# QuickRotor_V1.net
KiCad netlist of a schematic drawn in Altium Designer
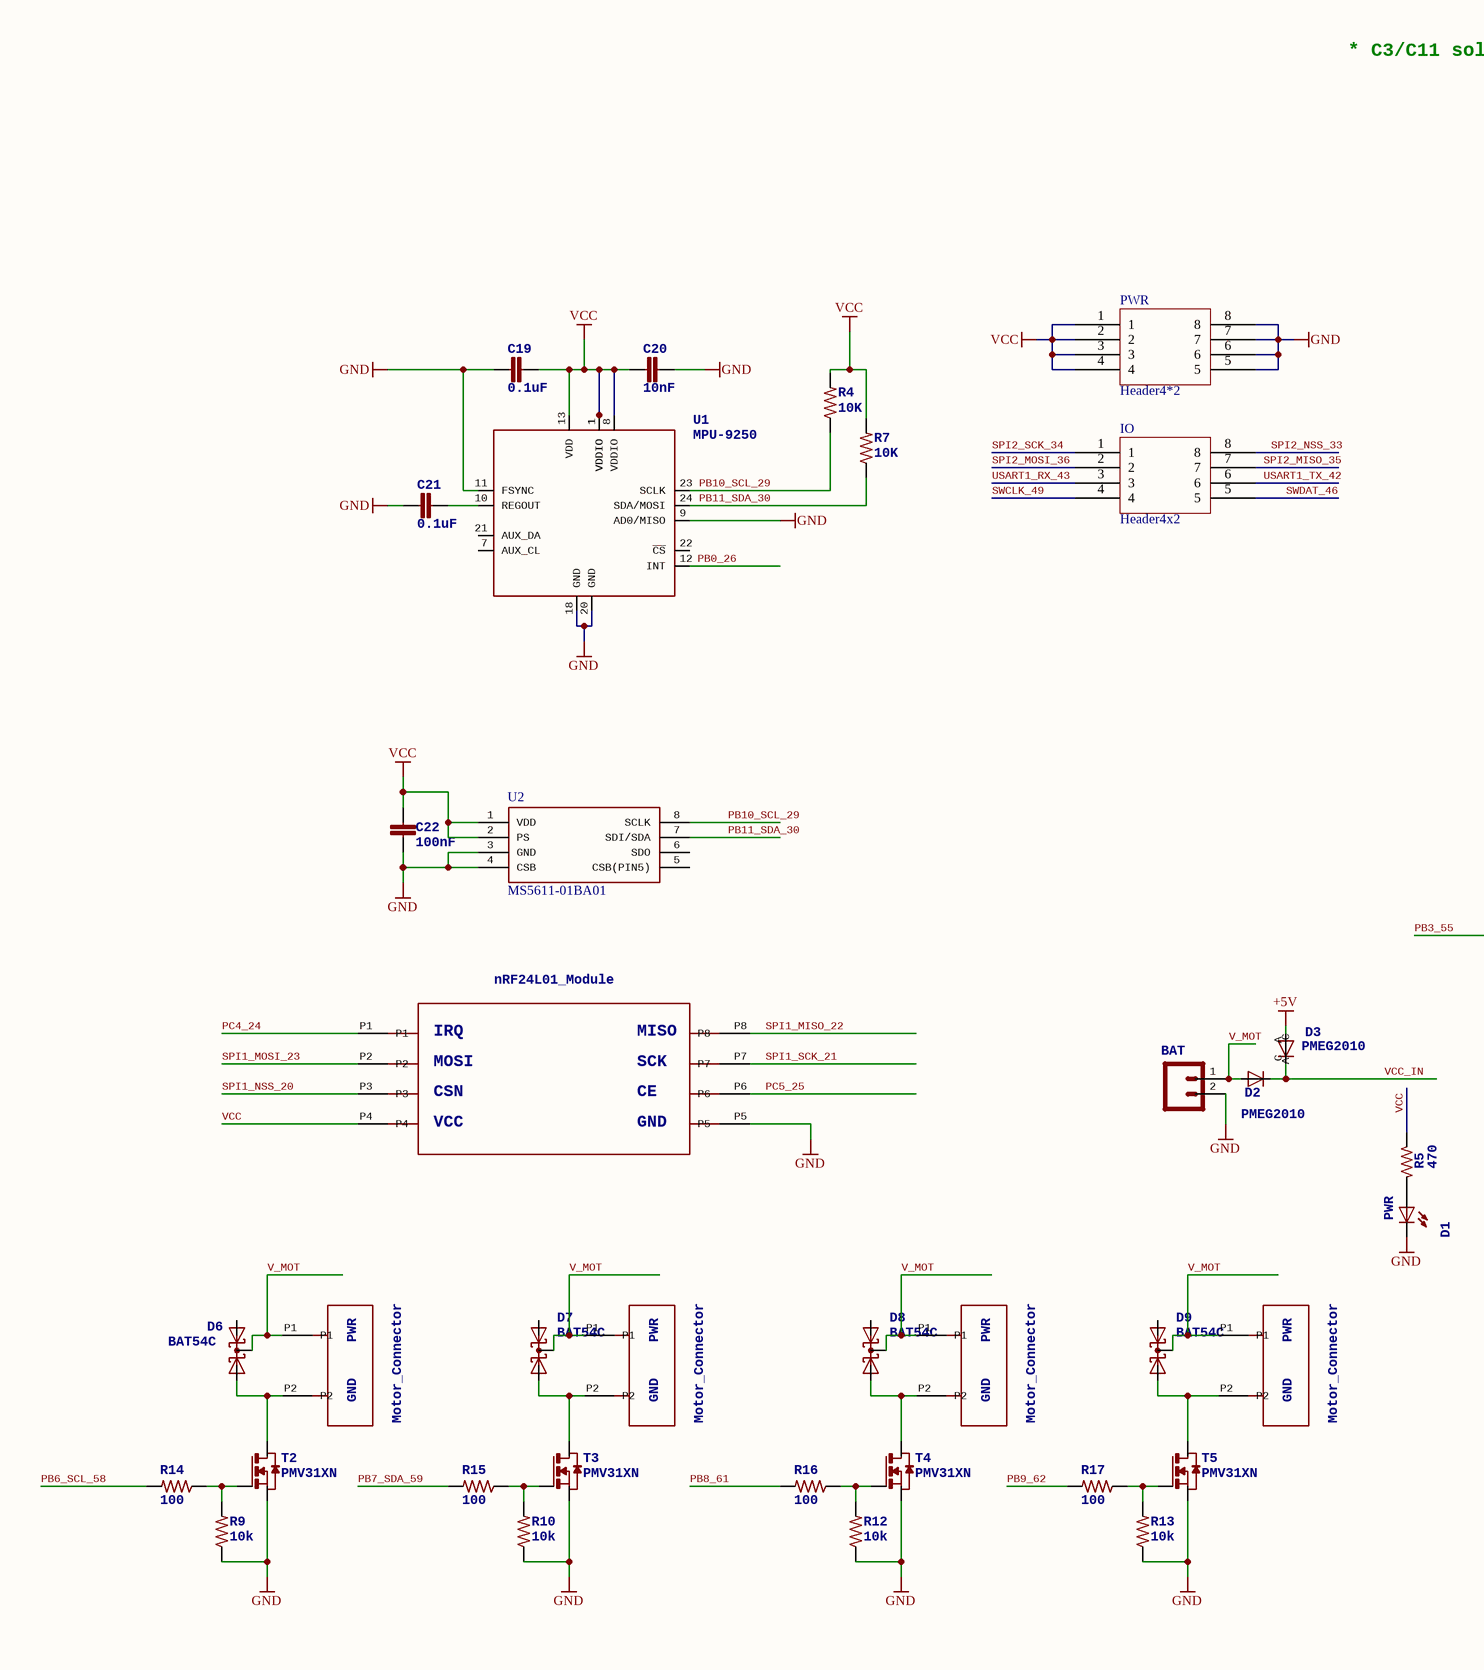
[diagram p0: QuickRotor_V1.SchDoc, left]
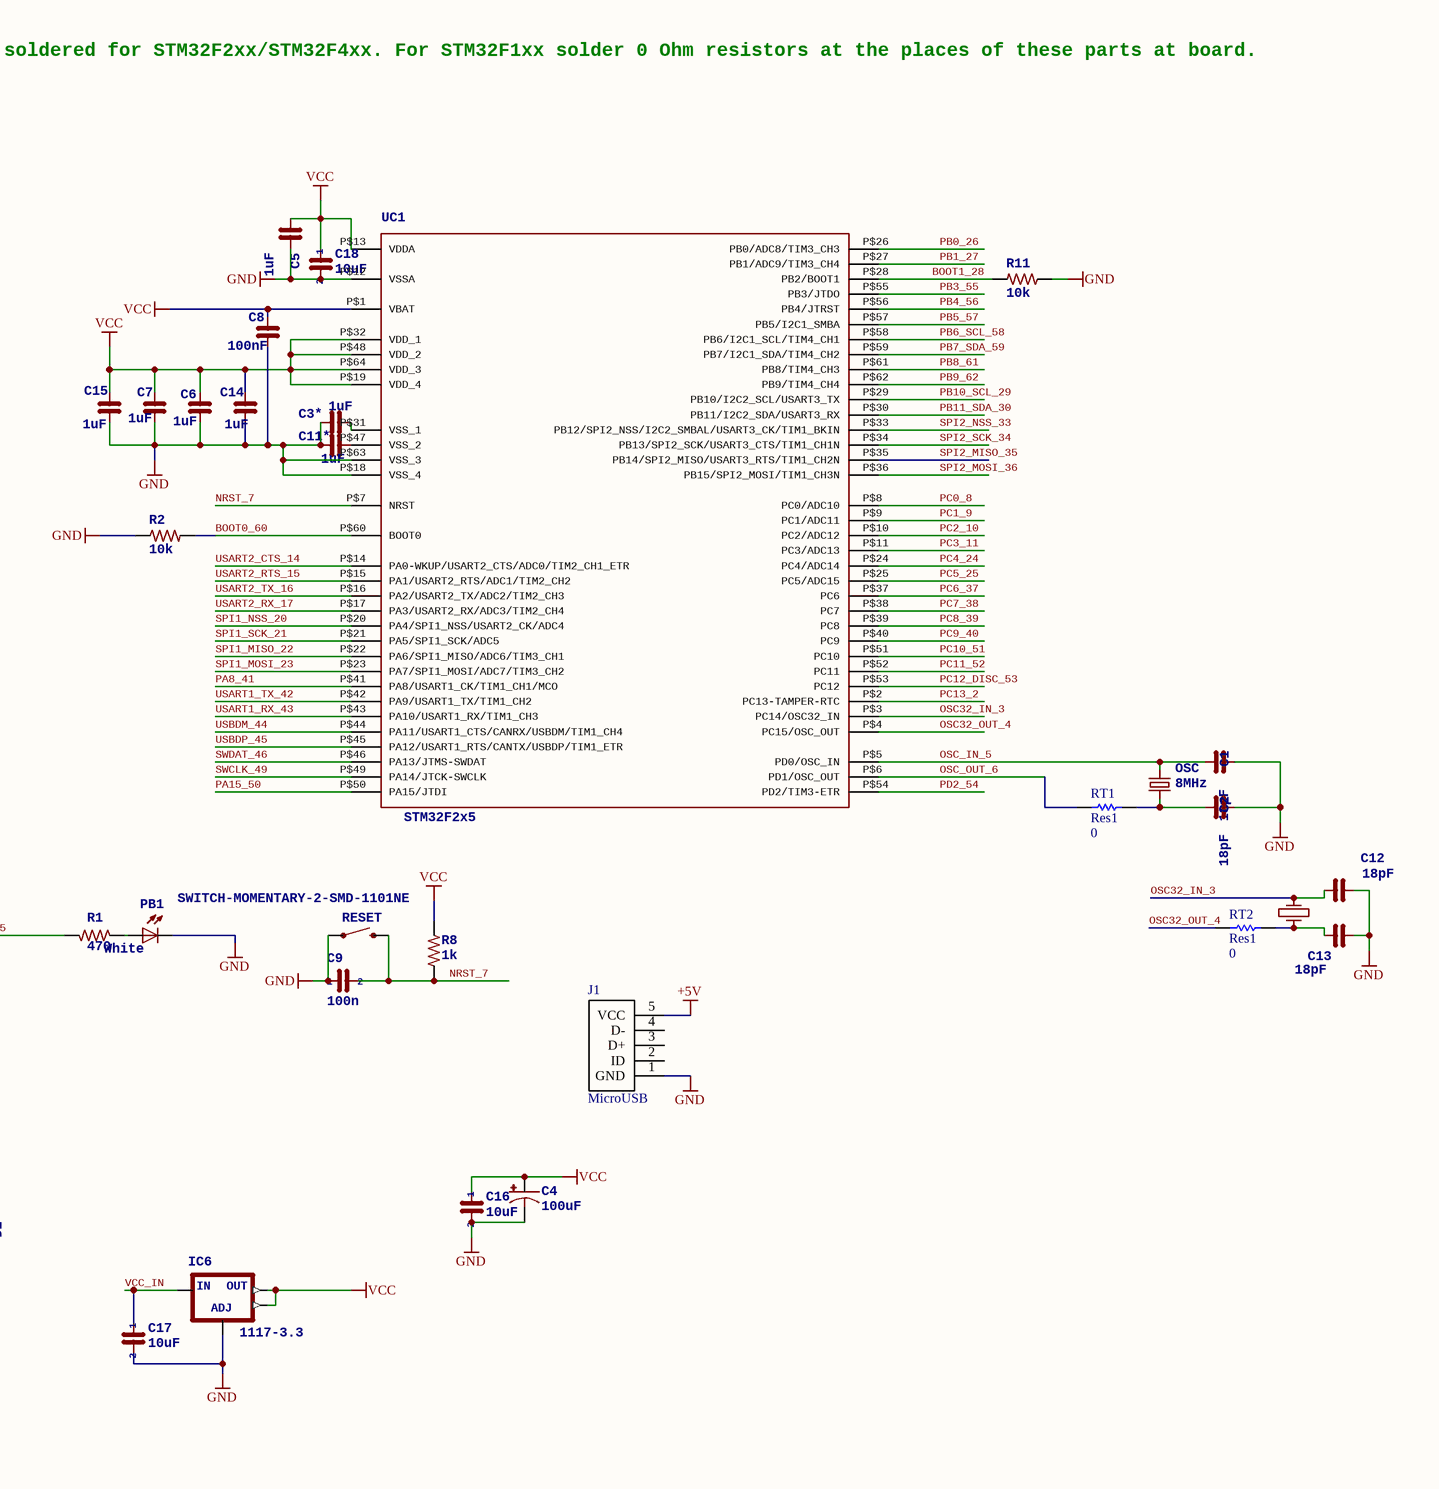
[diagram p1: QuickRotor_V1.SchDoc, right]

(export (version "E")
  (design (tool "Eeschema 10.0.6"))
  (components
    (comp (ref "24L01")
      (value "NRF24L01_MODULE")
      (footprint "NRF24L01_MODULE")
      (fields
        (field (name "NRF24L01_MODULE") "nRF24L01_Module")
        (field (name "IRQ") "IRQ")
        (field (name "MOSI") "MOSI")
        (field (name "CSN") "CSN")
        (field (name "VCC") "VCC")
        (field (name "GND") "GND")
        (field (name "CE") "CE")
        (field (name "SCK") "SCK")
        (field (name "MISO") "MISO")
      )
      (libsource (lib "RF_Modules") (part "NRF24L01_MODULE"))
    )
    (comp (ref "BAT")
      (value "M021X02_NO_SILK")
      (footprint "MOTOR_CONNECTOR")
      (libsource (lib "SparkFun_20110922_my") (part "M021X02_NO_SILK"))
    )
    (comp (ref "C1")
      (value "18pF")
      (footprint "0603-CAP")
      (description "NON-POLARIZED CAP")
      (libsource (lib "rc-master-smd") (part "C_0603"))
    )
    (comp (ref "C2")
      (value "18pF")
      (footprint "0603-CAP")
      (description "NON-POLARIZED CAP")
      (libsource (lib "rc-master-smd") (part "C_0603"))
    )
    (comp (ref "C3*")
      (value "1uF")
      (footprint "0603-CAP")
      (description "NON-POLARIZED CAP")
      (libsource (lib "rc-master-smd") (part "C_0603"))
    )
    (comp (ref "C4")
      (value "100uF")
      (footprint "EIA3528")
      (libsource (lib "SparkFun_20110922_my") (part "CAP_POL3528"))
    )
    (comp (ref "C5")
      (value "1uF")
      (footprint "0603-CAP")
      (description "NON-POLARIZED CAP")
      (libsource (lib "rc-master-smd") (part "C_0603"))
    )
    (comp (ref "C6")
      (value "1uF")
      (footprint "0603-CAP")
      (description "NON-POLARIZED CAP")
      (libsource (lib "rc-master-smd") (part "C_0603"))
    )
    (comp (ref "C7")
      (value "1uF")
      (footprint "0603-CAP")
      (description "NON-POLARIZED CAP")
      (libsource (lib "rc-master-smd") (part "C_0603"))
    )
    (comp (ref "C8")
      (value "100nF")
      (footprint "0603-CAP")
      (description "NON-POLARIZED CAP")
      (libsource (lib "rc-master-smd") (part "C_0603"))
    )
    (comp (ref "C9")
      (value "100n")
      (footprint "0603-CAP")
      (description "NON-POLARIZED CAP")
      (fields (field (name "1") "1") (field (name "2") "2"))
      (libsource (lib "") (part "C_0603_1"))
    )
    (comp (ref "C11*")
      (value "1uF")
      (footprint "0603-CAP")
      (description "NON-POLARIZED CAP")
      (libsource (lib "rc-master-smd") (part "C_0603"))
    )
    (comp (ref "C12")
      (value "18pF")
      (footprint "0603-CAP")
      (description "NON-POLARIZED CAP")
      (libsource (lib "rc-master-smd") (part "C_0603"))
    )
    (comp (ref "C13")
      (value "18pF")
      (footprint "0603-CAP")
      (description "NON-POLARIZED CAP")
      (libsource (lib "rc-master-smd") (part "C_0603"))
    )
    (comp (ref "C14")
      (value "1uF")
      (footprint "0603-CAP")
      (description "NON-POLARIZED CAP")
      (libsource (lib "rc-master-smd") (part "C_0603"))
    )
    (comp (ref "C15")
      (value "1uF")
      (footprint "0603-CAP")
      (description "NON-POLARIZED CAP")
      (libsource (lib "rc-master-smd") (part "C_0603"))
    )
    (comp (ref "C16")
      (value "10uF")
      (footprint "0805-CAP")
      (description "NON-POLARIZED CAP")
      (fields (field (name "1") "1") (field (name "2") "2"))
      (libsource (lib "rc-master-smd") (part "C_0805"))
    )
    (comp (ref "C17")
      (value "10uF")
      (footprint "0805-CAP")
      (description "NON-POLARIZED CAP")
      (fields (field (name "1") "1") (field (name "2") "2"))
      (libsource (lib "rc-master-smd") (part "C_0805"))
    )
    (comp (ref "C18")
      (value "10uF")
      (footprint "0805-CAP")
      (description "NON-POLARIZED CAP")
      (fields (field (name "1") "1") (field (name "2") "2"))
      (libsource (lib "rc-master-smd") (part "C_0805"))
    )
    (comp (ref "C19")
      (value "0.1uF")
      (footprint "0603-CAP")
      (description "CAPACITOR, European symbol")
      (libsource (lib "eagle-ltspice") (part "CC0603"))
    )
    (comp (ref "C20")
      (value "10nF")
      (footprint "0603-CAP")
      (description "CAPACITOR, European symbol")
      (libsource (lib "eagle-ltspice") (part "CC0603"))
    )
    (comp (ref "C21")
      (value "0.1uF")
      (footprint "0603-CAP")
      (description "CAPACITOR, European symbol")
      (libsource (lib "eagle-ltspice") (part "CC0603"))
    )
    (comp (ref "C22")
      (value "100nF")
      (footprint "0603-CAP")
      (description "CapacitorStandard 0603 ceramic capacitor, and 0.1\" leaded capacitor.")
      (libsource (lib "SparkFun-Passives") (part "CAP0603-CAP"))
    )
    (comp (ref "D1") (value "PWR") (footprint "0603-LED") (libsource (lib "led") (part "LEDCHIP-LED0603")))
    (comp (ref "D2") (value "PMEG2010") (footprint "SOD-323") (libsource (lib "") (part "DIODESOD-323_1")))
    (comp (ref "D3")
      (value "PMEG2010")
      (footprint "SOD-323")
      (libsource (lib "adafruit") (part "DIODESOD-323"))
    )
    (comp (ref "D6")
      (value "BAT54C")
      (footprint "SOT23")
      (description "Schottky Diodes   Source: Fairchild .. BAT54.pdf")
      (libsource (lib "diode") (part "BAT54C"))
    )
    (comp (ref "D7")
      (value "BAT54C")
      (footprint "SOT23")
      (description "Schottky Diodes   Source: Fairchild .. BAT54.pdf")
      (libsource (lib "diode") (part "BAT54C"))
    )
    (comp (ref "D8")
      (value "BAT54C")
      (footprint "SOT23")
      (description "Schottky Diodes   Source: Fairchild .. BAT54.pdf")
      (libsource (lib "diode") (part "BAT54C"))
    )
    (comp (ref "D9")
      (value "BAT54C")
      (footprint "SOT23")
      (description "Schottky Diodes   Source: Fairchild .. BAT54.pdf")
      (libsource (lib "diode") (part "BAT54C"))
    )
    (comp (ref "IC6")
      (value "1117-3.3")
      (footprint "SOT223")
      (fields (field (name "ADJ") "ADJ") (field (name "IN") "IN") (field (name "OUT") "OUT"))
      (libsource (lib "SparkFun_20110922_my") (part "V_REG_LM1117SOT223"))
    )
    (comp (ref "IO")
      (value "Header4x2")
      (footprint "Header4x2")
      (libsource (lib "Connector") (part "Component_1"))
    )
    (comp (ref "J1")
      (value "MicroUSB")
      (footprint "MicroUSB")
      (description "Imported")
      (libsource (lib "Connector") (part "MicroUSB"))
    )
    (comp (ref "OSC")
      (value "8MHz")
      (footprint "5032")
      (description "CrystalsVarious standard crystals. Proven footprints. Spark Fun Electronics SKU : COM-00534")
      (libsource (lib "SparkFun") (part "CRYSTAL5X3"))
    )
    (comp (ref "OSC2") (value "32.768kHz") (footprint "SM8") (libsource (lib "es") (part "CRYSTALL")))
    (comp (ref "PB1") (value "White") (footprint "0603-LED") (libsource (lib "led") (part "LEDCHIP-LED0603")))
    (comp (ref "PWR")
      (value "Header4*2")
      (footprint "Header4x2")
      (libsource (lib "Connector") (part "Component_1"))
    )
    (comp (ref "R1")
      (value "470")
      (footprint "0603-RES")
      (description "RESISTOR")
      (libsource (lib "") (part "R_0603_2"))
    )
    (comp (ref "R2")
      (value "10k")
      (footprint "0603-RES")
      (description "RESISTOR")
      (libsource (lib "") (part "R_0603_1"))
    )
    (comp (ref "R4")
      (value "10K")
      (footprint "0603-RES")
      (description "ResistorBasic schematic elements and footprints for 0603, 1206, and PTH resistors.")
      (libsource (lib "SparkFun-Resistors") (part "RESISTOR0603"))
    )
    (comp (ref "R5")
      (value "470")
      (footprint "0603-RES")
      (description "RESISTOR")
      (libsource (lib "") (part "R_0603_1"))
    )
    (comp (ref "R7")
      (value "10K")
      (footprint "0603-RES")
      (description "ResistorBasic schematic elements and footprints for 0603, 1206, and PTH resistors.")
      (libsource (lib "SparkFun-Resistors") (part "RESISTOR0603"))
    )
    (comp (ref "R8")
      (value "1k")
      (footprint "0603-RES")
      (description "RESISTOR")
      (libsource (lib "rc-master-smd") (part "R_0603"))
    )
    (comp (ref "R9")
      (value "10k")
      (footprint "0603-RES")
      (description "ResistorBasic schematic elements and footprints for 0603, 1206, and PTH resistors.")
      (libsource (lib "SparkFun-Resistors") (part "RESISTOR0603"))
    )
    (comp (ref "R10")
      (value "10k")
      (footprint "0603-RES")
      (description "ResistorBasic schematic elements and footprints for 0603, 1206, and PTH resistors.")
      (libsource (lib "SparkFun-Resistors") (part "RESISTOR0603"))
    )
    (comp (ref "R11")
      (value "10k")
      (footprint "0603-RES")
      (description "RESISTOR")
      (libsource (lib "") (part "R_0603_1"))
    )
    (comp (ref "R12")
      (value "10k")
      (footprint "0603-RES")
      (description "ResistorBasic schematic elements and footprints for 0603, 1206, and PTH resistors.")
      (libsource (lib "SparkFun-Resistors") (part "RESISTOR0603"))
    )
    (comp (ref "R13")
      (value "10k")
      (footprint "0603-RES")
      (description "ResistorBasic schematic elements and footprints for 0603, 1206, and PTH resistors.")
      (libsource (lib "SparkFun-Resistors") (part "RESISTOR0603"))
    )
    (comp (ref "R14")
      (value "100")
      (footprint "0603-RES")
      (description "ResistorBasic schematic elements and footprints for 0603, 1206, and PTH resistors.")
      (libsource (lib "SparkFun-Resistors") (part "RESISTOR0603"))
    )
    (comp (ref "R15")
      (value "100")
      (footprint "0603-RES")
      (description "ResistorBasic schematic elements and footprints for 0603, 1206, and PTH resistors.")
      (libsource (lib "SparkFun-Resistors") (part "RESISTOR0603"))
    )
    (comp (ref "R16")
      (value "100")
      (footprint "0603-RES")
      (description "ResistorBasic schematic elements and footprints for 0603, 1206, and PTH resistors.")
      (libsource (lib "SparkFun-Resistors") (part "RESISTOR0603"))
    )
    (comp (ref "R17")
      (value "100")
      (footprint "0603-RES")
      (description "ResistorBasic schematic elements and footprints for 0603, 1206, and PTH resistors.")
      (libsource (lib "SparkFun-Resistors") (part "RESISTOR0603"))
    )
    (comp (ref "RESET")
      (value "SWITCH-MOMENTARY-2-SMD-1101NE")
      (footprint "TACTILE-SWITCH-1101NE")
      (libsource (lib "SparkFun_20110922_my") (part "SWITCH-MOMENTARY-2-SMD-1101NE"))
    )
    (comp (ref "RT1")
      (value "Res1")
      (footprint "0603-RES")
      (description "Resistor")
      (fields (field (name "ALTIUM_VALUE") "0") (field (name "PUBLISHER") "Altium Limited"))
      (libsource (lib "Miscellaneous Devices") (part "Res1"))
    )
    (comp (ref "RT2")
      (value "Res1")
      (footprint "0603-RES")
      (description "Resistor")
      (fields (field (name "ALTIUM_VALUE") "0") (field (name "PUBLISHER") "Altium Limited"))
      (libsource (lib "Miscellaneous Devices") (part "Res1"))
    )
    (comp (ref "T2")
      (value "PMV31XN")
      (footprint "SOT-23")
      (description "MOS FET")
      (libsource (lib "zetex") (part "NMOSSOT23"))
    )
    (comp (ref "T3")
      (value "PMV31XN")
      (footprint "SOT-23")
      (description "MOS FET")
      (libsource (lib "zetex") (part "NMOSSOT23"))
    )
    (comp (ref "T4")
      (value "PMV31XN")
      (footprint "SOT-23")
      (description "MOS FET")
      (libsource (lib "zetex") (part "NMOSSOT23"))
    )
    (comp (ref "T5")
      (value "PMV31XN")
      (footprint "SOT-23")
      (description "MOS FET")
      (libsource (lib "zetex") (part "NMOSSOT23"))
    )
    (comp (ref "U$3")
      (value "MOTOR_CONNECTOR")
      (footprint "MOTOR_CONNECTOR")
      (fields
        (field (name "MOTOR_CONNECTOR") "Motor_Connector")
        (field (name "PWR") "PWR")
        (field (name "GND") "GND")
      )
      (libsource (lib "QuickRotor_Library") (part "MOTOR_CONNECTOR"))
    )
    (comp (ref "U$4")
      (value "MOTOR_CONNECTOR")
      (footprint "MOTOR_CONNECTOR")
      (fields
        (field (name "MOTOR_CONNECTOR") "Motor_Connector")
        (field (name "PWR") "PWR")
        (field (name "GND") "GND")
      )
      (libsource (lib "QuickRotor_Library") (part "MOTOR_CONNECTOR"))
    )
    (comp (ref "U$5")
      (value "MOTOR_CONNECTOR")
      (footprint "MOTOR_CONNECTOR")
      (fields
        (field (name "MOTOR_CONNECTOR") "Motor_Connector")
        (field (name "PWR") "PWR")
        (field (name "GND") "GND")
      )
      (libsource (lib "QuickRotor_Library") (part "MOTOR_CONNECTOR"))
    )
    (comp (ref "U$6")
      (value "MOTOR_CONNECTOR")
      (footprint "MOTOR_CONNECTOR")
      (fields
        (field (name "MOTOR_CONNECTOR") "Motor_Connector")
        (field (name "PWR") "PWR")
        (field (name "GND") "GND")
      )
      (libsource (lib "QuickRotor_Library") (part "MOTOR_CONNECTOR"))
    )
    (comp (ref "U1")
      (value "MPU-9250")
      (footprint "QFN-24/3MM")
      (description "GYRO/ACCEL/COMPASS/9-AXIS")
      (libsource (lib "QuickRotor_V1") (part "MPU-9250"))
    )
    (comp (ref "U2")
      (value "MS5611-01BA01")
      (footprint "MS5611-01BA01")
      (libsource (lib "QuickRotor_V1") (part "MS5611-01BA01"))
    )
    (comp (ref "UC1")
      (value "STM32F2x5")
      (footprint "TQFP-10X10-64")
      (libsource (lib "st-microelectronics") (part "STM32F103"))
    )
  )
  (nets
    (net (code "1") (name "+5V") (class "Default")
      (node (ref "D3") (pin "A") (pinfunction "A_A") (pintype "passive"))
      (node (ref "J1") (pin "5") (pinfunction "VCC_5") (pintype "passive"))
    )
    (net (code "2") (name "/BOOT0_60") (class "Default")
      (node (ref "R2") (pin "1") (pinfunction "1_1") (pintype "passive"))
      (node (ref "UC1") (pin "P$60") (pinfunction "BOOT0_P$60") (pintype "passive"))
    )
    (net (code "3") (name "/BOOT1_28") (class "Default")
      (node (ref "R11") (pin "2") (pinfunction "2_2") (pintype "passive"))
      (node (ref "UC1") (pin "P$28") (pinfunction "PB2/BOOT1_P$28") (pintype "passive"))
    )
    (net (code "4") (name "/NRST_7") (class "Default")
      (node (ref "C9") (pin "2") (pinfunction "2_2") (pintype "passive"))
      (node (ref "R8") (pin "1") (pinfunction "1_1") (pintype "passive"))
      (node (ref "RESET") (pin "P$2") (pinfunction "2_P$2") (pintype "passive"))
      (node (ref "UC1") (pin "P$7") (pinfunction "NRST_P$7") (pintype "passive"))
    )
    (net (code "5") (name "/OSC32_IN_3") (class "Default")
      (node (ref "C12") (pin "2") (pinfunction "2_2") (pintype "passive"))
      (node (ref "OSC2") (pin "1") (pinfunction "P$1_1") (pintype "passive"))
      (node (ref "UC1") (pin "P$3") (pinfunction "PC14/OSC32_IN_P$3") (pintype "passive"))
    )
    (net (code "6") (name "/OSC32_OUT_4") (class "Default")
      (node (ref "RT2") (pin "1") (pinfunction "1_1") (pintype "passive"))
      (node (ref "UC1") (pin "P$4") (pinfunction "PC15/OSC_OUT_P$4") (pintype "passive"))
    )
    (net (code "7") (name "/OSC_IN_5") (class "Default")
      (node (ref "C1") (pin "2") (pinfunction "2_2") (pintype "passive"))
      (node (ref "OSC") (pin "3") (pinfunction "2_3") (pintype "passive"))
      (node (ref "UC1") (pin "P$5") (pinfunction "PD0/OSC_IN_P$5") (pintype "passive"))
    )
    (net (code "8") (name "/OSC_OUT_6") (class "Default")
      (node (ref "RT1") (pin "1") (pinfunction "1_1") (pintype "passive"))
      (node (ref "UC1") (pin "P$6") (pinfunction "PD1/OSC_OUT_P$6") (pintype "passive"))
    )
    (net (code "9") (name "/PA8_41") (class "Default")
      (node (ref "UC1") (pin "P$41") (pinfunction "PA8/USART1_CK/TIM1_CH1/MCO_P$41") (pintype "passive"))
    )
    (net (code "10") (name "/PA15_50") (class "Default")
      (node (ref "UC1") (pin "P$50") (pinfunction "PA15/JTDI_P$50") (pintype "passive"))
    )
    (net (code "11") (name "/PB0_26") (class "Default")
      (node (ref "U1") (pin "12") (pinfunction "INT_12") (pintype "passive"))
      (node (ref "UC1") (pin "P$26") (pinfunction "PB0/ADC8/TIM3_CH3_P$26") (pintype "passive"))
    )
    (net (code "12") (name "/PB1_27") (class "Default")
      (node (ref "UC1") (pin "P$27") (pinfunction "PB1/ADC9/TIM3_CH4_P$27") (pintype "passive"))
    )
    (net (code "13") (name "/PB3_55") (class "Default")
      (node (ref "R1") (pin "2") (pinfunction "2_2") (pintype "passive"))
      (node (ref "UC1") (pin "P$55") (pinfunction "PB3/JTDO_P$55") (pintype "passive"))
    )
    (net (code "14") (name "/PB4_56") (class "Default")
      (node (ref "UC1") (pin "P$56") (pinfunction "PB4/JTRST_P$56") (pintype "passive"))
    )
    (net (code "15") (name "/PB5_57") (class "Default")
      (node (ref "UC1") (pin "P$57") (pinfunction "PB5/I2C1_SMBA_P$57") (pintype "passive"))
    )
    (net (code "16") (name "/PB6_SCL_58") (class "Default")
      (node (ref "R14") (pin "2") (pinfunction "2_2") (pintype "passive"))
      (node (ref "UC1") (pin "P$58") (pinfunction "PB6/I2C1_SCL/TIM4_CH1_P$58") (pintype "passive"))
    )
    (net (code "17") (name "/PB7_SDA_59") (class "Default")
      (node (ref "R15") (pin "2") (pinfunction "2_2") (pintype "passive"))
      (node (ref "UC1") (pin "P$59") (pinfunction "PB7/I2C1_SDA/TIM4_CH2_P$59") (pintype "passive"))
    )
    (net (code "18") (name "/PB8_61") (class "Default")
      (node (ref "R16") (pin "2") (pinfunction "2_2") (pintype "passive"))
      (node (ref "UC1") (pin "P$61") (pinfunction "PB8/TIM4_CH3_P$61") (pintype "passive"))
    )
    (net (code "19") (name "/PB9_62") (class "Default")
      (node (ref "R17") (pin "2") (pinfunction "2_2") (pintype "passive"))
      (node (ref "UC1") (pin "P$62") (pinfunction "PB9/TIM4_CH4_P$62") (pintype "passive"))
    )
    (net (code "20") (name "/PB10_SCL_29") (class "Default")
      (node (ref "R4") (pin "1") (pinfunction "1_1") (pintype "passive"))
      (node (ref "U1") (pin "23") (pinfunction "SCLK_23") (pintype "passive"))
      (node (ref "U2") (pin "8") (pinfunction "SCLK_8") (pintype "passive"))
      (node (ref "UC1") (pin "P$29") (pinfunction "PB10/I2C2_SCL/USART3_TX_P$29") (pintype "passive"))
    )
    (net (code "21") (name "/PB11_SDA_30") (class "Default")
      (node (ref "R7") (pin "1") (pinfunction "1_1") (pintype "passive"))
      (node (ref "U1") (pin "24") (pinfunction "SDA/MOSI_24") (pintype "passive"))
      (node (ref "U2") (pin "7") (pinfunction "SDI/SDA_7") (pintype "passive"))
      (node (ref "UC1") (pin "P$30") (pinfunction "PB11/I2C2_SDA/USART3_RX_P$30") (pintype "passive"))
    )
    (net (code "22") (name "/PC0_8") (class "Default")
      (node (ref "UC1") (pin "P$8") (pinfunction "PC0/ADC10_P$8") (pintype "passive"))
    )
    (net (code "23") (name "/PC1_9") (class "Default")
      (node (ref "UC1") (pin "P$9") (pinfunction "PC1/ADC11_P$9") (pintype "passive"))
    )
    (net (code "24") (name "/PC2_10") (class "Default")
      (node (ref "UC1") (pin "P$10") (pinfunction "PC2/ADC12_P$10") (pintype "passive"))
    )
    (net (code "25") (name "/PC3_11") (class "Default")
      (node (ref "UC1") (pin "P$11") (pinfunction "PC3/ADC13_P$11") (pintype "passive"))
    )
    (net (code "26") (name "/PC4_24") (class "Default")
      (node (ref "24L01") (pin "P1") (pinfunction "P1_P1") (pintype "passive"))
      (node (ref "UC1") (pin "P$24") (pinfunction "PC4/ADC14_P$24") (pintype "passive"))
    )
    (net (code "27") (name "/PC5_25") (class "Default")
      (node (ref "24L01") (pin "P6") (pinfunction "P6_P6") (pintype "passive"))
      (node (ref "UC1") (pin "P$25") (pinfunction "PC5/ADC15_P$25") (pintype "passive"))
    )
    (net (code "28") (name "/PC6_37") (class "Default")
      (node (ref "UC1") (pin "P$37") (pinfunction "PC6_P$37") (pintype "passive"))
    )
    (net (code "29") (name "/PC7_38") (class "Default")
      (node (ref "UC1") (pin "P$38") (pinfunction "PC7_P$38") (pintype "passive"))
    )
    (net (code "30") (name "/PC8_39") (class "Default")
      (node (ref "UC1") (pin "P$39") (pinfunction "PC8_P$39") (pintype "passive"))
    )
    (net (code "31") (name "/PC9_40") (class "Default")
      (node (ref "UC1") (pin "P$40") (pinfunction "PC9_P$40") (pintype "passive"))
    )
    (net (code "32") (name "/PC10_51") (class "Default")
      (node (ref "UC1") (pin "P$51") (pinfunction "PC10_P$51") (pintype "passive"))
    )
    (net (code "33") (name "/PC11_52") (class "Default")
      (node (ref "UC1") (pin "P$52") (pinfunction "PC11_P$52") (pintype "passive"))
    )
    (net (code "34") (name "/PC12_DISC_53") (class "Default")
      (node (ref "UC1") (pin "P$53") (pinfunction "PC12_P$53") (pintype "passive"))
    )
    (net (code "35") (name "/PC13_2") (class "Default")
      (node (ref "UC1") (pin "P$2") (pinfunction "PC13-TAMPER-RTC_P$2") (pintype "passive"))
    )
    (net (code "36") (name "/PD2_54") (class "Default")
      (node (ref "UC1") (pin "P$54") (pinfunction "PD2/TIM3-ETR_P$54") (pintype "passive"))
    )
    (net (code "37") (name "/SPI1_MISO_22") (class "Default")
      (node (ref "24L01") (pin "P8") (pinfunction "P8_P8") (pintype "passive"))
      (node (ref "UC1") (pin "P$22") (pinfunction "PA6/SPI1_MISO/ADC6/TIM3_CH1_P$22") (pintype "passive"))
    )
    (net (code "38") (name "/SPI1_MOSI_23") (class "Default")
      (node (ref "24L01") (pin "P2") (pinfunction "P2_P2") (pintype "passive"))
      (node (ref "UC1") (pin "P$23") (pinfunction "PA7/SPI1_MOSI/ADC7/TIM3_CH2_P$23") (pintype "passive"))
    )
    (net (code "39") (name "/SPI1_NSS_20") (class "Default")
      (node (ref "24L01") (pin "P3") (pinfunction "P3_P3") (pintype "passive"))
      (node (ref "UC1") (pin "P$20") (pinfunction "PA4/SPI1_NSS/USART2_CK/ADC4_P$20") (pintype "passive"))
    )
    (net (code "40") (name "/SPI1_SCK_21") (class "Default")
      (node (ref "24L01") (pin "P7") (pinfunction "P7_P7") (pintype "passive"))
      (node (ref "UC1") (pin "P$21") (pinfunction "PA5/SPI1_SCK/ADC5_P$21") (pintype "passive"))
    )
    (net (code "41") (name "/SPI2_MISO_35") (class "Default")
      (node (ref "IO") (pin "7") (pinfunction "7_7") (pintype "passive"))
      (node (ref "UC1") (pin "P$35") (pinfunction "PB14/SPI2_MISO/USART3_RTS/TIM1_CH2N_P$35") (pintype "passive"))
    )
    (net (code "42") (name "/SPI2_MOSI_36") (class "Default")
      (node (ref "IO") (pin "2") (pinfunction "2_2") (pintype "passive"))
      (node (ref "UC1") (pin "P$36") (pinfunction "PB15/SPI2_MOSI/TIM1_CH3N_P$36") (pintype "passive"))
    )
    (net (code "43") (name "/SPI2_NSS_33") (class "Default")
      (node (ref "IO") (pin "8") (pinfunction "8_8") (pintype "passive"))
      (node (ref "UC1") (pin "P$33") (pinfunction "PB12/SPI2_NSS/I2C2_SMBAL/USART3_CK/TIM1_BKIN_P$33") (pintype "passive"))
    )
    (net (code "44") (name "/SPI2_SCK_34") (class "Default")
      (node (ref "IO") (pin "1") (pinfunction "1_1") (pintype "passive"))
      (node (ref "UC1") (pin "P$34") (pinfunction "PB13/SPI2_SCK/USART3_CTS/TIM1_CH1N_P$34") (pintype "passive"))
    )
    (net (code "45") (name "/SWCLK_49") (class "Default")
      (node (ref "IO") (pin "4") (pinfunction "4_4") (pintype "passive"))
      (node (ref "UC1") (pin "P$49") (pinfunction "PA14/JTCK-SWCLK_P$49") (pintype "passive"))
    )
    (net (code "46") (name "/SWDAT_46") (class "Default")
      (node (ref "IO") (pin "5") (pinfunction "5_5") (pintype "passive"))
      (node (ref "UC1") (pin "P$46") (pinfunction "PA13/JTMS-SWDAT_P$46") (pintype "passive"))
    )
    (net (code "47") (name "/USART1_RX_43") (class "Default")
      (node (ref "IO") (pin "3") (pinfunction "3_3") (pintype "passive"))
      (node (ref "UC1") (pin "P$43") (pinfunction "PA10/USART1_RX/TIM1_CH3_P$43") (pintype "passive"))
    )
    (net (code "48") (name "/USART1_TX_42") (class "Default")
      (node (ref "IO") (pin "6") (pinfunction "6_6") (pintype "passive"))
      (node (ref "UC1") (pin "P$42") (pinfunction "PA9/USART1_TX/TIM1_CH2_P$42") (pintype "passive"))
    )
    (net (code "49") (name "/USART2_CTS_14") (class "Default")
      (node (ref "UC1") (pin "P$14") (pinfunction "PA0-WKUP/USART2_CTS/ADC0/TIM2_CH1_ETR_P$14") (pintype "passive"))
    )
    (net (code "50") (name "/USART2_RTS_15") (class "Default")
      (node (ref "UC1") (pin "P$15") (pinfunction "PA1/USART2_RTS/ADC1/TIM2_CH2_P$15") (pintype "passive"))
    )
    (net (code "51") (name "/USART2_RX_17") (class "Default")
      (node (ref "UC1") (pin "P$17") (pinfunction "PA3/USART2_RX/ADC3/TIM2_CH4_P$17") (pintype "passive"))
    )
    (net (code "52") (name "/USART2_TX_16") (class "Default")
      (node (ref "UC1") (pin "P$16") (pinfunction "PA2/USART2_TX/ADC2/TIM2_CH3_P$16") (pintype "passive"))
    )
    (net (code "53") (name "/USBDM_44") (class "Default")
      (node (ref "UC1") (pin "P$44") (pinfunction "PA11/USART1_CTS/CANRX/USBDM/TIM1_CH4_P$44") (pintype "passive"))
    )
    (net (code "54") (name "/USBDP_45") (class "Default")
      (node (ref "UC1") (pin "P$45") (pinfunction "PA12/USART1_RTS/CANTX/USBDP/TIM1_ETR_P$45") (pintype "passive"))
    )
    (net (code "55") (name "/VCC_IN") (class "Default")
      (node (ref "C17") (pin "1") (pinfunction "1_1") (pintype "passive"))
      (node (ref "D2") (pin "C") (pinfunction "C_C") (pintype "passive"))
      (node (ref "D3") (pin "C") (pinfunction "C_C") (pintype "passive"))
      (node (ref "IC6") (pin "3") (pinfunction "IN_3") (pintype "passive"))
    )
    (net (code "56") (name "/V_MOT") (class "Default")
      (node (ref "BAT") (pin "1") (pinfunction "1_1") (pintype "passive"))
      (node (ref "D2") (pin "A") (pinfunction "A_A") (pintype "passive"))
      (node (ref "D6") (pin "3") (pinfunction "CC_3") (pintype "passive"))
      (node (ref "D7") (pin "3") (pinfunction "CC_3") (pintype "passive"))
      (node (ref "D8") (pin "3") (pinfunction "CC_3") (pintype "passive"))
      (node (ref "D9") (pin "3") (pinfunction "CC_3") (pintype "passive"))
      (node (ref "U$3") (pin "P1") (pinfunction "P1_P1") (pintype "passive"))
      (node (ref "U$4") (pin "P1") (pinfunction "P1_P1") (pintype "passive"))
      (node (ref "U$5") (pin "P1") (pinfunction "P1_P1") (pintype "passive"))
      (node (ref "U$6") (pin "P1") (pinfunction "P1_P1") (pintype "passive"))
    )
    (net (code "57") (name "GND") (class "Default")
      (node (ref "24L01") (pin "P5") (pinfunction "P5_P5") (pintype "passive"))
      (node (ref "BAT") (pin "2") (pinfunction "2_2") (pintype "passive"))
      (node (ref "C1") (pin "1") (pinfunction "1_1") (pintype "passive"))
      (node (ref "C11*") (pin "2") (pinfunction "2_2") (pintype "passive"))
      (node (ref "C12") (pin "1") (pinfunction "1_1") (pintype "passive"))
      (node (ref "C13") (pin "1") (pinfunction "1_1") (pintype "passive"))
      (node (ref "C14") (pin "1") (pinfunction "1_1") (pintype "passive"))
      (node (ref "C15") (pin "1") (pinfunction "1_1") (pintype "passive"))
      (node (ref "C16") (pin "2") (pinfunction "2_2") (pintype "passive"))
      (node (ref "C17") (pin "2") (pinfunction "2_2") (pintype "passive"))
      (node (ref "C18") (pin "2") (pinfunction "2_2") (pintype "passive"))
      (node (ref "C19") (pin "1") (pinfunction "1_1") (pintype "passive"))
      (node (ref "C2") (pin "1") (pinfunction "1_1") (pintype "passive"))
      (node (ref "C20") (pin "2") (pinfunction "2_2") (pintype "passive"))
      (node (ref "C21") (pin "1") (pinfunction "1_1") (pintype "passive"))
      (node (ref "C22") (pin "2") (pinfunction "2_2") (pintype "passive"))
      (node (ref "C3*") (pin "2") (pinfunction "2_2") (pintype "passive"))
      (node (ref "C4") (pin "C") (pinfunction "-_C") (pintype "passive"))
      (node (ref "C5") (pin "1") (pinfunction "1_1") (pintype "passive"))
      (node (ref "C6") (pin "1") (pinfunction "1_1") (pintype "passive"))
      (node (ref "C7") (pin "1") (pinfunction "1_1") (pintype "passive"))
      (node (ref "C8") (pin "1") (pinfunction "1_1") (pintype "passive"))
      (node (ref "C9") (pin "1") (pinfunction "1_1") (pintype "passive"))
      (node (ref "D1") (pin "C") (pinfunction "C_C") (pintype "passive"))
      (node (ref "IC6") (pin "1") (pinfunction "ADJ_1") (pintype "passive"))
      (node (ref "J1") (pin "1") (pinfunction "GND_1") (pintype "passive"))
      (node (ref "PB1") (pin "C") (pinfunction "C_C") (pintype "passive"))
      (node (ref "PWR") (pin "5") (pinfunction "5_5") (pintype "passive"))
      (node (ref "PWR") (pin "6") (pinfunction "6_6") (pintype "passive"))
      (node (ref "PWR") (pin "7") (pinfunction "7_7") (pintype "passive"))
      (node (ref "PWR") (pin "8") (pinfunction "8_8") (pintype "passive"))
      (node (ref "R10") (pin "1") (pinfunction "1_1") (pintype "passive"))
      (node (ref "R11") (pin "1") (pinfunction "1_1") (pintype "passive"))
      (node (ref "R12") (pin "1") (pinfunction "1_1") (pintype "passive"))
      (node (ref "R13") (pin "1") (pinfunction "1_1") (pintype "passive"))
      (node (ref "R2") (pin "2") (pinfunction "2_2") (pintype "passive"))
      (node (ref "R9") (pin "1") (pinfunction "1_1") (pintype "passive"))
      (node (ref "RESET") (pin "P$1") (pinfunction "1_P$1") (pintype "passive"))
      (node (ref "T2") (pin "2") (pinfunction "S_2") (pintype "passive"))
      (node (ref "T3") (pin "2") (pinfunction "S_2") (pintype "passive"))
      (node (ref "T4") (pin "2") (pinfunction "S_2") (pintype "passive"))
      (node (ref "T5") (pin "2") (pinfunction "S_2") (pintype "passive"))
      (node (ref "U1") (pin "11") (pinfunction "FSYNC_11") (pintype "passive"))
      (node (ref "U1") (pin "18") (pinfunction "GND_18") (pintype "passive"))
      (node (ref "U1") (pin "20") (pinfunction "GND_20") (pintype "passive"))
      (node (ref "U1") (pin "9") (pinfunction "AD0/MISO_9") (pintype "passive"))
      (node (ref "U2") (pin "3") (pinfunction "GND_3") (pintype "passive"))
      (node (ref "U2") (pin "4") (pinfunction "CSB_4") (pintype "passive"))
      (node (ref "UC1") (pin "P$12") (pinfunction "VSSA_P$12") (pintype "power_in"))
      (node (ref "UC1") (pin "P$18") (pinfunction "VSS_4_P$18") (pintype "power_in"))
      (node (ref "UC1") (pin "P$63") (pinfunction "VSS_3_P$63") (pintype "power_in"))
    )
    (net (code "58") (name "Net-(C2-Pad2)") (class "Default")
      (node (ref "C2") (pin "2") (pinfunction "2_2") (pintype "passive"))
      (node (ref "OSC") (pin "1") (pinfunction "1_1") (pintype "passive"))
      (node (ref "RT1") (pin "2") (pinfunction "2_2") (pintype "passive"))
    )
    (net (code "59") (name "Net-(D1-PadA)") (class "Default")
      (node (ref "D1") (pin "A") (pinfunction "A_A") (pintype "passive"))
      (node (ref "R5") (pin "2") (pinfunction "2_2") (pintype "passive"))
    )
    (net (code "60") (name "Net-(D6-A2)") (class "Default")
      (node (ref "D6") (pin "2") (pinfunction "A2_2") (pintype "passive"))
      (node (ref "T2") (pin "1") (pinfunction "D_1") (pintype "passive"))
      (node (ref "U$3") (pin "P2") (pinfunction "P2_P2") (pintype "passive"))
    )
    (net (code "61") (name "Net-(D7-A2)") (class "Default")
      (node (ref "D7") (pin "2") (pinfunction "A2_2") (pintype "passive"))
      (node (ref "T3") (pin "1") (pinfunction "D_1") (pintype "passive"))
      (node (ref "U$4") (pin "P2") (pinfunction "P2_P2") (pintype "passive"))
    )
    (net (code "62") (name "Net-(D8-A2)") (class "Default")
      (node (ref "D8") (pin "2") (pinfunction "A2_2") (pintype "passive"))
      (node (ref "T4") (pin "1") (pinfunction "D_1") (pintype "passive"))
      (node (ref "U$5") (pin "P2") (pinfunction "P2_P2") (pintype "passive"))
    )
    (net (code "63") (name "Net-(D9-A2)") (class "Default")
      (node (ref "D9") (pin "2") (pinfunction "A2_2") (pintype "passive"))
      (node (ref "T5") (pin "1") (pinfunction "D_1") (pintype "passive"))
      (node (ref "U$6") (pin "P2") (pinfunction "P2_P2") (pintype "passive"))
    )
    (net (code "64") (name "Net-(OSC2-P$2)") (class "Default")
      (node (ref "C13") (pin "2") (pinfunction "2_2") (pintype "passive"))
      (node (ref "OSC2") (pin "4") (pinfunction "P$2_4") (pintype "passive"))
      (node (ref "RT2") (pin "2") (pinfunction "2_2") (pintype "passive"))
    )
    (net (code "65") (name "Net-(PB1-PadA)") (class "Default")
      (node (ref "PB1") (pin "A") (pinfunction "A_A") (pintype "passive"))
      (node (ref "R1") (pin "1") (pinfunction "1_1") (pintype "passive"))
    )
    (net (code "66") (name "Net-(T2-G)") (class "Default")
      (node (ref "R14") (pin "1") (pinfunction "1_1") (pintype "passive"))
      (node (ref "R9") (pin "2") (pinfunction "2_2") (pintype "passive"))
      (node (ref "T2") (pin "3") (pinfunction "G_3") (pintype "passive"))
    )
    (net (code "67") (name "Net-(T3-G)") (class "Default")
      (node (ref "R10") (pin "2") (pinfunction "2_2") (pintype "passive"))
      (node (ref "R15") (pin "1") (pinfunction "1_1") (pintype "passive"))
      (node (ref "T3") (pin "3") (pinfunction "G_3") (pintype "passive"))
    )
    (net (code "68") (name "Net-(T4-G)") (class "Default")
      (node (ref "R12") (pin "2") (pinfunction "2_2") (pintype "passive"))
      (node (ref "R16") (pin "1") (pinfunction "1_1") (pintype "passive"))
      (node (ref "T4") (pin "3") (pinfunction "G_3") (pintype "passive"))
    )
    (net (code "69") (name "Net-(T5-G)") (class "Default")
      (node (ref "R13") (pin "2") (pinfunction "2_2") (pintype "passive"))
      (node (ref "R17") (pin "1") (pinfunction "1_1") (pintype "passive"))
      (node (ref "T5") (pin "3") (pinfunction "G_3") (pintype "passive"))
    )
    (net (code "70") (name "Net-(U1-REGOUT)") (class "Default")
      (node (ref "C21") (pin "2") (pinfunction "2_2") (pintype "passive"))
      (node (ref "U1") (pin "10") (pinfunction "REGOUT_10") (pintype "passive"))
    )
    (net (code "71") (name "Net-(UC1-VSS_1)") (class "Default")
      (node (ref "C3*") (pin "1") (pinfunction "1_1") (pintype "passive"))
      (node (ref "UC1") (pin "P$31") (pinfunction "VSS_1_P$31") (pintype "power_in"))
    )
    (net (code "72") (name "Net-(UC1-VSS_2)") (class "Default")
      (node (ref "C11*") (pin "1") (pinfunction "1_1") (pintype "passive"))
      (node (ref "UC1") (pin "P$47") (pinfunction "VSS_2_P$47") (pintype "power_in"))
    )
    (net (code "73") (name "VCC") (class "Default")
      (node (ref "24L01") (pin "P4") (pinfunction "P4_P4") (pintype "passive"))
      (node (ref "C14") (pin "2") (pinfunction "2_2") (pintype "passive"))
      (node (ref "C15") (pin "2") (pinfunction "2_2") (pintype "passive"))
      (node (ref "C16") (pin "1") (pinfunction "1_1") (pintype "passive"))
      (node (ref "C18") (pin "1") (pinfunction "1_1") (pintype "passive"))
      (node (ref "C19") (pin "2") (pinfunction "2_2") (pintype "passive"))
      (node (ref "C20") (pin "1") (pinfunction "1_1") (pintype "passive"))
      (node (ref "C22") (pin "1") (pinfunction "1_1") (pintype "passive"))
      (node (ref "C4") (pin "A") (pinfunction "+_A") (pintype "passive"))
      (node (ref "C5") (pin "2") (pinfunction "2_2") (pintype "passive"))
      (node (ref "C6") (pin "2") (pinfunction "2_2") (pintype "passive"))
      (node (ref "C7") (pin "2") (pinfunction "2_2") (pintype "passive"))
      (node (ref "C8") (pin "2") (pinfunction "2_2") (pintype "passive"))
      (node (ref "IC6") (pin "2") (pinfunction "OUT_2") (pintype "output"))
      (node (ref "IC6") (pin "4") (pinfunction "OUT_4") (pintype "output"))
      (node (ref "PWR") (pin "1") (pinfunction "1_1") (pintype "passive"))
      (node (ref "PWR") (pin "2") (pinfunction "2_2") (pintype "passive"))
      (node (ref "PWR") (pin "3") (pinfunction "3_3") (pintype "passive"))
      (node (ref "PWR") (pin "4") (pinfunction "4_4") (pintype "passive"))
      (node (ref "R4") (pin "2") (pinfunction "2_2") (pintype "passive"))
      (node (ref "R5") (pin "1") (pinfunction "1_1") (pintype "passive"))
      (node (ref "R7") (pin "2") (pinfunction "2_2") (pintype "passive"))
      (node (ref "R8") (pin "2") (pinfunction "2_2") (pintype "passive"))
      (node (ref "U1") (pin "1") (pinfunction "VDDIO_1") (pintype "passive"))
      (node (ref "U1") (pin "13") (pinfunction "VDD_13") (pintype "passive"))
      (node (ref "U1") (pin "8") (pinfunction "VDDIO_8") (pintype "passive"))
      (node (ref "U2") (pin "1") (pinfunction "VDD_1") (pintype "passive"))
      (node (ref "U2") (pin "2") (pinfunction "PS_2") (pintype "passive"))
      (node (ref "UC1") (pin "P$1") (pinfunction "VBAT_P$1") (pintype "power_in"))
      (node (ref "UC1") (pin "P$13") (pinfunction "VDDA_P$13") (pintype "power_in"))
      (node (ref "UC1") (pin "P$19") (pinfunction "VDD_4_P$19") (pintype "power_in"))
      (node (ref "UC1") (pin "P$32") (pinfunction "VDD_1_P$32") (pintype "power_in"))
      (node (ref "UC1") (pin "P$48") (pinfunction "VDD_2_P$48") (pintype "power_in"))
      (node (ref "UC1") (pin "P$64") (pinfunction "VDD_3_P$64") (pintype "power_in"))
    )
    (net (code "74") (name "unconnected-(D6-A1-Pad1)") (class "Default")
      (node (ref "D6") (pin "1") (pinfunction "A1_1") (pintype "passive"))
    )
    (net (code "75") (name "unconnected-(D7-A1-Pad1)") (class "Default")
      (node (ref "D7") (pin "1") (pinfunction "A1_1") (pintype "passive"))
    )
    (net (code "76") (name "unconnected-(D8-A1-Pad1)") (class "Default")
      (node (ref "D8") (pin "1") (pinfunction "A1_1") (pintype "passive"))
    )
    (net (code "77") (name "unconnected-(D9-A1-Pad1)") (class "Default")
      (node (ref "D9") (pin "1") (pinfunction "A1_1") (pintype "passive"))
    )
    (net (code "78") (name "unconnected-(J1-D+-Pad3)") (class "Default")
      (node (ref "J1") (pin "3") (pinfunction "D+_3") (pintype "passive"))
    )
    (net (code "79") (name "unconnected-(J1-D--Pad4)") (class "Default")
      (node (ref "J1") (pin "4") (pinfunction "D-_4") (pintype "passive"))
    )
    (net (code "80") (name "unconnected-(J1-ID-Pad2)") (class "Default")
      (node (ref "J1") (pin "2") (pinfunction "ID_2") (pintype "passive"))
    )
    (net (code "81") (name "unconnected-(U1-AUX_CL-Pad7)") (class "Default")
      (node (ref "U1") (pin "7") (pinfunction "AUX_CL_7") (pintype "passive"))
    )
    (net (code "82") (name "unconnected-(U1-AUX_DA-Pad21)") (class "Default")
      (node (ref "U1") (pin "21") (pinfunction "AUX_DA_21") (pintype "passive"))
    )
    (net (code "83") (name "unconnected-(U1-~{CS}-Pad22)") (class "Default")
      (node (ref "U1") (pin "22") (pinfunction "~{CS}_22") (pintype "passive"))
    )
    (net (code "84") (name "unconnected-(U2-CSB(PIN5)-Pad5)") (class "Default")
      (node (ref "U2") (pin "5") (pinfunction "CSB(PIN5)_5") (pintype "passive"))
    )
    (net (code "85") (name "unconnected-(U2-SDO-Pad6)") (class "Default")
      (node (ref "U2") (pin "6") (pinfunction "SDO_6") (pintype "passive"))
    )
  )
)
